# atmega8.net
KiCad netlist of a schematic drawn in EAGLE
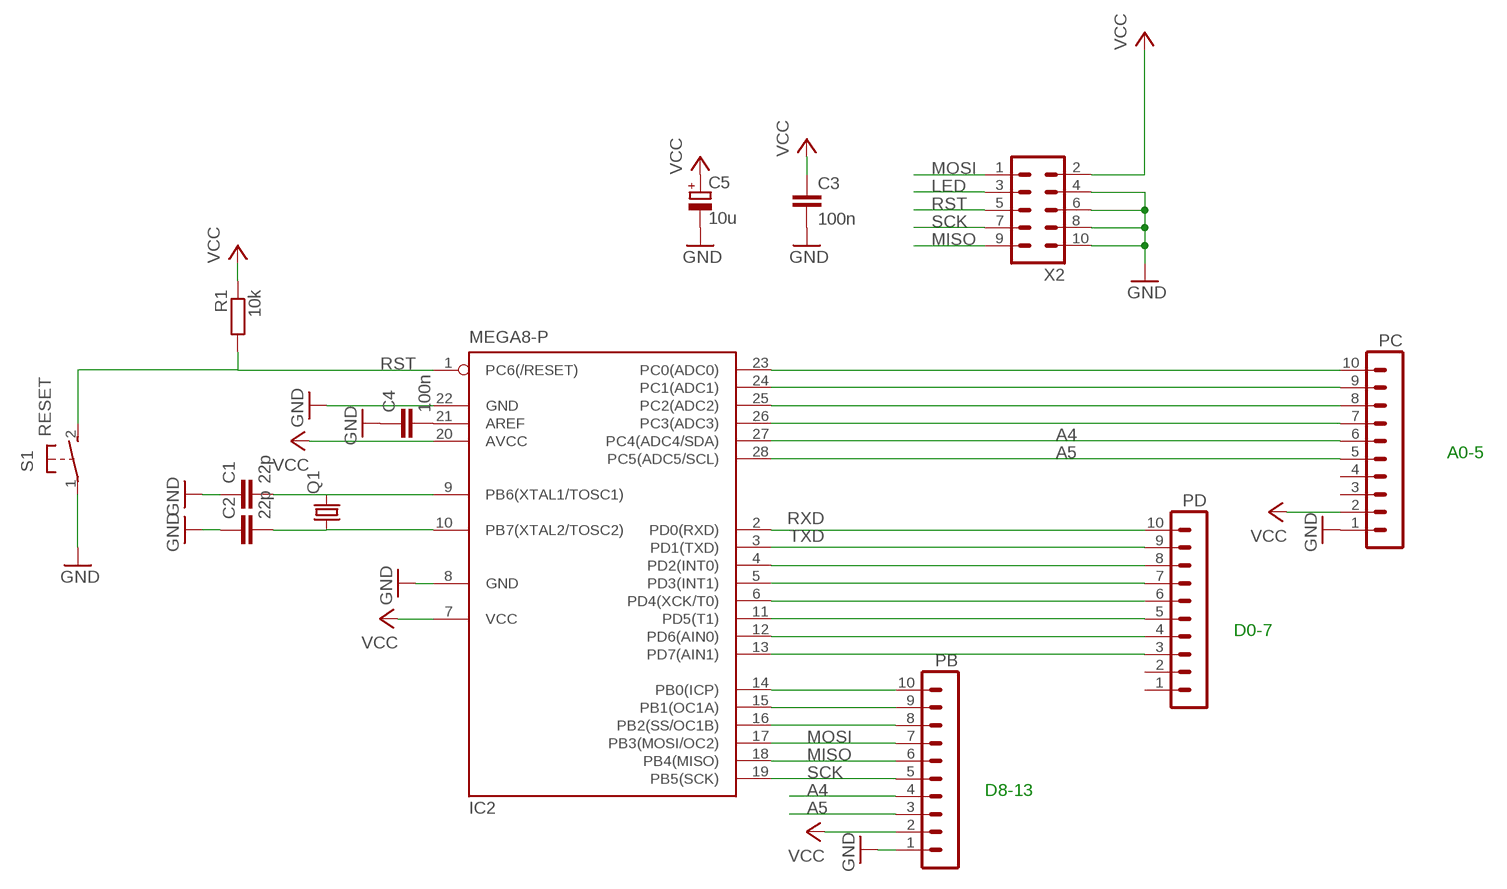
[diagram p0: schematic, sheet 1]

(export (version "E")
  (design (tool "Eeschema 10.0.6"))
  (components
    (comp (ref "C1")
      (value "22p")
      (footprint "eagle-import:C025-024X044")
      (libsource (lib "eagle-import") (part "C-EU025-024X044"))
    )
    (comp (ref "C2")
      (value "22p")
      (footprint "eagle-import:C050-025X075")
      (libsource (lib "eagle-import") (part "C-EU050-025X075"))
    )
    (comp (ref "C3")
      (value "100n")
      (footprint "eagle-import:C025-024X044")
      (libsource (lib "eagle-import") (part "C-EU025-024X044"))
    )
    (comp (ref "C4")
      (value "100n")
      (footprint "eagle-import:C025-024X044")
      (libsource (lib "eagle-import") (part "C-EU025-024X044"))
    )
    (comp (ref "C5")
      (value "10u")
      (footprint "eagle-import:E2,5-6E")
      (libsource (lib "eagle-import") (part "CPOL-EUE2,5-6E"))
    )
    (comp (ref "IC2")
      (value "MEGA8-P")
      (footprint "eagle-import:DIL28-3")
      (libsource (lib "eagle-import") (part "MEGA8-P"))
    )
    (comp (ref "PB")
      (value "MA10-1W")
      (footprint "eagle-import:MA10-1W")
      (libsource (lib "eagle-import") (part "MA10-1W"))
    )
    (comp (ref "PC")
      (value "MA10-1W")
      (footprint "eagle-import:MA10-1W")
      (libsource (lib "eagle-import") (part "MA10-1W"))
    )
    (comp (ref "PD")
      (value "MA10-1W")
      (footprint "eagle-import:MA10-1W")
      (libsource (lib "eagle-import") (part "MA10-1W"))
    )
    (comp (ref "Q1")
      (value "CRYSTALTC26V")
      (footprint "eagle-import:TC26V")
      (libsource (lib "eagle-import") (part "CRYSTALTC26V"))
    )
    (comp (ref "R1")
      (value "10k")
      (footprint "eagle-import:0204_7")
      (libsource (lib "eagle-import") (part "R-EU_0204/7"))
    )
    (comp (ref "S1")
      (value "RESET")
      (footprint "eagle-import:B3F-31XX")
      (libsource (lib "eagle-import") (part "31-XX"))
    )
    (comp (ref "X2")
      (value "ML10L")
      (footprint "eagle-import:ML10L")
      (libsource (lib "eagle-import") (part "ML10L"))
    )
  )
  (nets
    (net (code "1") (name "/A4") (class "Default")
      (node (ref "IC2") (pin "27") (pinfunction "PC4(ADC4/SDA)_27") (pintype "bidirectional"))
      (node (ref "PB") (pin "4") (pinfunction "4_4") (pintype "passive"))
      (node (ref "PC") (pin "6") (pinfunction "6_6") (pintype "passive"))
    )
    (net (code "2") (name "/A5") (class "Default")
      (node (ref "IC2") (pin "28") (pinfunction "PC5(ADC5/SCL)_28") (pintype "bidirectional"))
      (node (ref "PB") (pin "3") (pinfunction "3_3") (pintype "passive"))
      (node (ref "PC") (pin "5") (pinfunction "5_5") (pintype "passive"))
    )
    (net (code "3") (name "/LED") (class "Default")
      (node (ref "X2") (pin "3") (pinfunction "3_3") (pintype "passive"))
    )
    (net (code "4") (name "/MISO") (class "Default")
      (node (ref "IC2") (pin "18") (pinfunction "PB4(MISO)_18") (pintype "bidirectional"))
      (node (ref "PB") (pin "6") (pinfunction "6_6") (pintype "passive"))
      (node (ref "X2") (pin "9") (pinfunction "9_9") (pintype "passive"))
    )
    (net (code "5") (name "/MOSI") (class "Default")
      (node (ref "IC2") (pin "17") (pinfunction "PB3(MOSI/OC2)_17") (pintype "bidirectional"))
      (node (ref "PB") (pin "7") (pinfunction "7_7") (pintype "passive"))
      (node (ref "X2") (pin "1") (pinfunction "1_1") (pintype "passive"))
    )
    (net (code "6") (name "/RST") (class "Default")
      (node (ref "X2") (pin "5") (pinfunction "5_5") (pintype "passive"))
    )
    (net (code "7") (name "/RXD") (class "Default")
      (node (ref "IC2") (pin "2") (pinfunction "PD0(RXD)_2") (pintype "bidirectional"))
      (node (ref "PD") (pin "10") (pinfunction "10_10") (pintype "passive"))
    )
    (net (code "8") (name "/SCK") (class "Default")
      (node (ref "IC2") (pin "19") (pinfunction "PB5(SCK)_19") (pintype "bidirectional"))
      (node (ref "PB") (pin "5") (pinfunction "5_5") (pintype "passive"))
      (node (ref "X2") (pin "7") (pinfunction "7_7") (pintype "passive"))
    )
    (net (code "9") (name "/TXD") (class "Default")
      (node (ref "IC2") (pin "3") (pinfunction "PD1(TXD)_3") (pintype "bidirectional"))
      (node (ref "PD") (pin "9") (pinfunction "9_9") (pintype "passive"))
    )
    (net (code "10") (name "GND") (class "Default")
      (node (ref "C1") (pin "1") (pinfunction "1_1") (pintype "passive"))
      (node (ref "C2") (pin "1") (pinfunction "1_1") (pintype "passive"))
      (node (ref "C3") (pin "2") (pinfunction "2_2") (pintype "passive"))
      (node (ref "C4") (pin "1") (pinfunction "1_1") (pintype "passive"))
      (node (ref "C5") (pin "-") (pinfunction "-_-") (pintype "passive"))
      (node (ref "IC2") (pin "22") (pinfunction "GND_22") (pintype "power_in"))
      (node (ref "IC2") (pin "8") (pinfunction "GND_8") (pintype "power_in"))
      (node (ref "PB") (pin "1") (pinfunction "1_1") (pintype "passive"))
      (node (ref "PC") (pin "1") (pinfunction "1_1") (pintype "passive"))
      (node (ref "S1") (pin "1") (pinfunction "P_1") (pintype "passive"))
      (node (ref "X2") (pin "10") (pinfunction "10_10") (pintype "passive"))
      (node (ref "X2") (pin "4") (pinfunction "4_4") (pintype "passive"))
      (node (ref "X2") (pin "6") (pinfunction "6_6") (pintype "passive"))
      (node (ref "X2") (pin "8") (pinfunction "8_8") (pintype "passive"))
    )
    (net (code "11") (name "Net-(IC2-AREF)") (class "Default")
      (node (ref "C4") (pin "2") (pinfunction "2_2") (pintype "passive"))
      (node (ref "IC2") (pin "21") (pinfunction "AREF_21") (pintype "passive"))
    )
    (net (code "12") (name "Net-(IC2-PB0(ICP))") (class "Default")
      (node (ref "IC2") (pin "14") (pinfunction "PB0(ICP)_14") (pintype "bidirectional"))
      (node (ref "PB") (pin "10") (pinfunction "10_10") (pintype "passive"))
    )
    (net (code "13") (name "Net-(IC2-PB1(OC1A))") (class "Default")
      (node (ref "IC2") (pin "15") (pinfunction "PB1(OC1A)_15") (pintype "bidirectional"))
      (node (ref "PB") (pin "9") (pinfunction "9_9") (pintype "passive"))
    )
    (net (code "14") (name "Net-(IC2-PB2(SS{slash}OC1B))") (class "Default")
      (node (ref "IC2") (pin "16") (pinfunction "PB2(SS/OC1B)_16") (pintype "bidirectional"))
      (node (ref "PB") (pin "8") (pinfunction "8_8") (pintype "passive"))
    )
    (net (code "15") (name "Net-(IC2-PB6(XTAL1{slash}TOSC1))") (class "Default")
      (node (ref "C1") (pin "2") (pinfunction "2_2") (pintype "passive"))
      (node (ref "IC2") (pin "9") (pinfunction "PB6(XTAL1/TOSC1)_9") (pintype "bidirectional"))
      (node (ref "Q1") (pin "2") (pinfunction "2_2") (pintype "passive"))
    )
    (net (code "16") (name "Net-(IC2-PB7(XTAL2{slash}TOSC2))") (class "Default")
      (node (ref "C2") (pin "2") (pinfunction "2_2") (pintype "passive"))
      (node (ref "IC2") (pin "10") (pinfunction "PB7(XTAL2/TOSC2)_10") (pintype "bidirectional"))
      (node (ref "Q1") (pin "1") (pinfunction "1_1") (pintype "passive"))
    )
    (net (code "17") (name "Net-(IC2-PC0(ADC0))") (class "Default")
      (node (ref "IC2") (pin "23") (pinfunction "PC0(ADC0)_23") (pintype "bidirectional"))
      (node (ref "PC") (pin "10") (pinfunction "10_10") (pintype "passive"))
    )
    (net (code "18") (name "Net-(IC2-PC1(ADC1))") (class "Default")
      (node (ref "IC2") (pin "24") (pinfunction "PC1(ADC1)_24") (pintype "bidirectional"))
      (node (ref "PC") (pin "9") (pinfunction "9_9") (pintype "passive"))
    )
    (net (code "19") (name "Net-(IC2-PC2(ADC2))") (class "Default")
      (node (ref "IC2") (pin "25") (pinfunction "PC2(ADC2)_25") (pintype "bidirectional"))
      (node (ref "PC") (pin "8") (pinfunction "8_8") (pintype "passive"))
    )
    (net (code "20") (name "Net-(IC2-PC3(ADC3))") (class "Default")
      (node (ref "IC2") (pin "26") (pinfunction "PC3(ADC3)_26") (pintype "bidirectional"))
      (node (ref "PC") (pin "7") (pinfunction "7_7") (pintype "passive"))
    )
    (net (code "21") (name "Net-(IC2-PC6({slash}RESET))") (class "Default")
      (node (ref "IC2") (pin "1") (pinfunction "PC6(/RESET)_1") (pintype "bidirectional"))
      (node (ref "R1") (pin "2") (pinfunction "2_2") (pintype "passive"))
      (node (ref "S1") (pin "2") (pinfunction "S_2") (pintype "passive"))
    )
    (net (code "22") (name "Net-(IC2-PD2(INT0))") (class "Default")
      (node (ref "IC2") (pin "4") (pinfunction "PD2(INT0)_4") (pintype "bidirectional"))
      (node (ref "PD") (pin "8") (pinfunction "8_8") (pintype "passive"))
    )
    (net (code "23") (name "Net-(IC2-PD3(INT1))") (class "Default")
      (node (ref "IC2") (pin "5") (pinfunction "PD3(INT1)_5") (pintype "bidirectional"))
      (node (ref "PD") (pin "7") (pinfunction "7_7") (pintype "passive"))
    )
    (net (code "24") (name "Net-(IC2-PD4(XCK{slash}T0))") (class "Default")
      (node (ref "IC2") (pin "6") (pinfunction "PD4(XCK/T0)_6") (pintype "bidirectional"))
      (node (ref "PD") (pin "6") (pinfunction "6_6") (pintype "passive"))
    )
    (net (code "25") (name "Net-(IC2-PD5(T1))") (class "Default")
      (node (ref "IC2") (pin "11") (pinfunction "PD5(T1)_11") (pintype "bidirectional"))
      (node (ref "PD") (pin "5") (pinfunction "5_5") (pintype "passive"))
    )
    (net (code "26") (name "Net-(IC2-PD6(AIN0))") (class "Default")
      (node (ref "IC2") (pin "12") (pinfunction "PD6(AIN0)_12") (pintype "bidirectional"))
      (node (ref "PD") (pin "4") (pinfunction "4_4") (pintype "passive"))
    )
    (net (code "27") (name "Net-(IC2-PD7(AIN1))") (class "Default")
      (node (ref "IC2") (pin "13") (pinfunction "PD7(AIN1)_13") (pintype "bidirectional"))
      (node (ref "PD") (pin "3") (pinfunction "3_3") (pintype "passive"))
    )
    (net (code "28") (name "VCC") (class "Default")
      (node (ref "C3") (pin "1") (pinfunction "1_1") (pintype "passive"))
      (node (ref "C5") (pin "+") (pinfunction "+_+") (pintype "passive"))
      (node (ref "IC2") (pin "20") (pinfunction "AVCC_20") (pintype "power_in"))
      (node (ref "IC2") (pin "7") (pinfunction "VCC_7") (pintype "power_in"))
      (node (ref "PB") (pin "2") (pinfunction "2_2") (pintype "passive"))
      (node (ref "PC") (pin "2") (pinfunction "2_2") (pintype "passive"))
      (node (ref "R1") (pin "1") (pinfunction "1_1") (pintype "passive"))
      (node (ref "X2") (pin "2") (pinfunction "2_2") (pintype "passive"))
    )
    (net (code "29") (name "unconnected-(PC-Pad3)") (class "Default")
      (node (ref "PC") (pin "3") (pinfunction "3_3") (pintype "passive"))
    )
    (net (code "30") (name "unconnected-(PC-Pad4)") (class "Default")
      (node (ref "PC") (pin "4") (pinfunction "4_4") (pintype "passive"))
    )
    (net (code "31") (name "unconnected-(PD-Pad1)") (class "Default")
      (node (ref "PD") (pin "1") (pinfunction "1_1") (pintype "passive"))
    )
    (net (code "32") (name "unconnected-(PD-Pad2)") (class "Default")
      (node (ref "PD") (pin "2") (pinfunction "2_2") (pintype "passive"))
    )
  )
)
